# StartStopSwitch.net
KiCad netlist of a schematic drawn in EAGLE
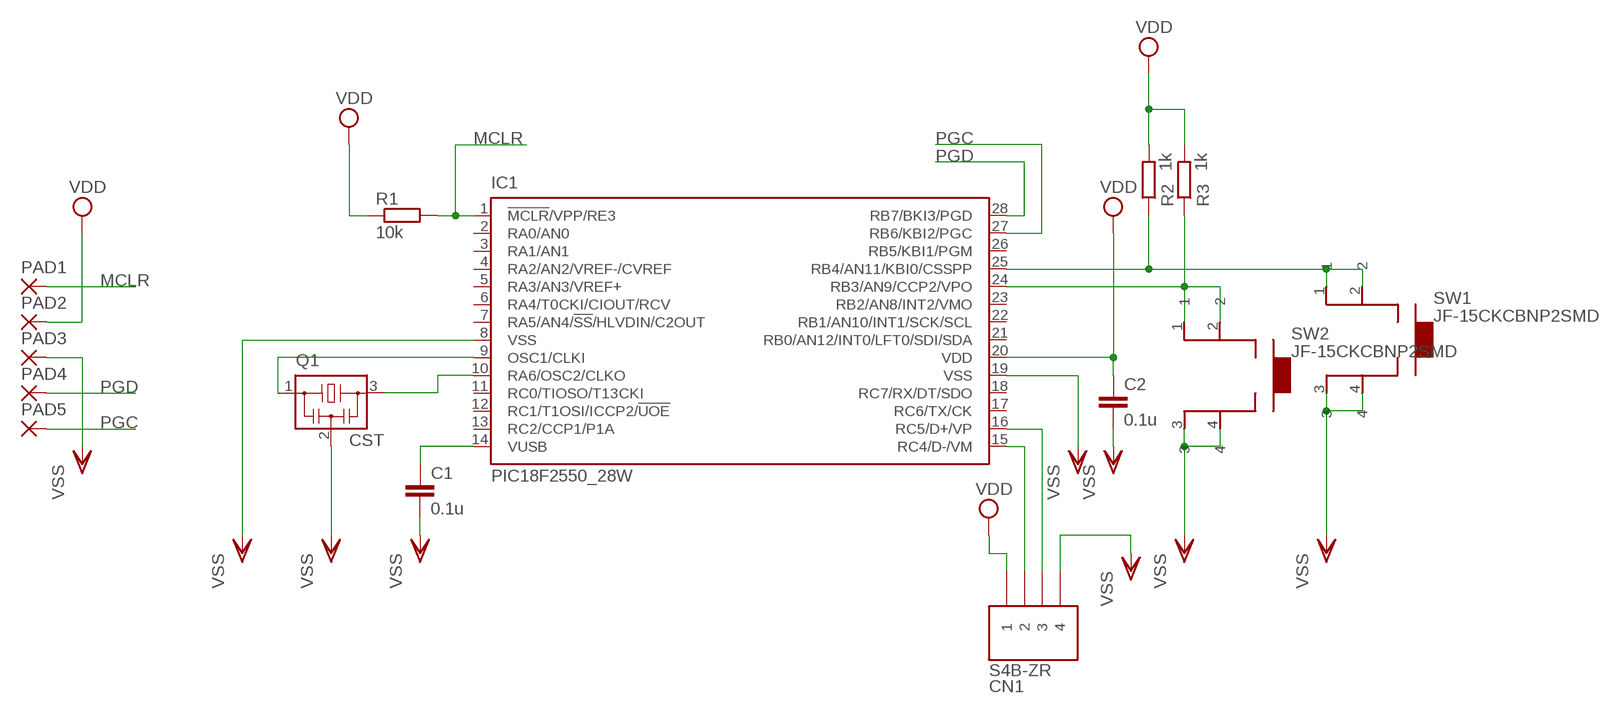
[diagram p0: schematic, sheet 1]

(export (version "E")
  (design (tool "Eeschema 10.0.6"))
  (components
    (comp (ref "C1")
      (value "0.1u")
      (footprint "eagle-import:C2012")
      (libsource (lib "eagle-import") (part "C-EUC2012"))
    )
    (comp (ref "C2")
      (value "0.1u")
      (footprint "eagle-import:C2012")
      (libsource (lib "eagle-import") (part "C-EUC2012"))
    )
    (comp (ref "CN1")
      (value "S4B-ZR")
      (footprint "eagle-import:S4B-ZR")
      (libsource (lib "eagle-import") (part "S4B-ZR"))
    )
    (comp (ref "IC1")
      (value "PIC18F2550_28W")
      (footprint "eagle-import:SO28W")
      (fields (field (name "MF") "MICROCHIP") (field (name "MPN") "PIC18F2550-I/SO"))
      (libsource (lib "eagle-import") (part "PIC18F2_28W550"))
    )
    (comp (ref "PAD1")
      (value "WIREPADSMD1,27-254")
      (footprint "eagle-import:SMD1,27-2,54")
      (libsource (lib "eagle-import") (part "WIREPADSMD1,27-254"))
    )
    (comp (ref "PAD2")
      (value "WIREPADSMD1,27-254")
      (footprint "eagle-import:SMD1,27-2,54")
      (libsource (lib "eagle-import") (part "WIREPADSMD1,27-254"))
    )
    (comp (ref "PAD3")
      (value "WIREPADSMD1,27-254")
      (footprint "eagle-import:SMD1,27-2,54")
      (libsource (lib "eagle-import") (part "WIREPADSMD1,27-254"))
    )
    (comp (ref "PAD4")
      (value "WIREPADSMD1,27-254")
      (footprint "eagle-import:SMD1,27-2,54")
      (libsource (lib "eagle-import") (part "WIREPADSMD1,27-254"))
    )
    (comp (ref "PAD5")
      (value "WIREPADSMD1,27-254")
      (footprint "eagle-import:SMD1,27-2,54")
      (libsource (lib "eagle-import") (part "WIREPADSMD1,27-254"))
    )
    (comp (ref "Q1")
      (value "CST")
      (footprint "eagle-import:CSTCR6M-MINI")
      (libsource (lib "eagle-import") (part "CSTCRMINI"))
    )
    (comp (ref "R1")
      (value "10k")
      (footprint "eagle-import:R0805")
      (libsource (lib "eagle-import") (part "R-EU_R0805"))
    )
    (comp (ref "R2")
      (value "1k")
      (footprint "eagle-import:R0805")
      (libsource (lib "eagle-import") (part "R-EU_R0805"))
    )
    (comp (ref "R3")
      (value "1k")
      (footprint "eagle-import:R0805")
      (libsource (lib "eagle-import") (part "R-EU_R0805"))
    )
    (comp (ref "SW1")
      (value "JF-15CKCBNP2SMD")
      (footprint "eagle-import:JF-15CKCBNP2-SMD")
      (libsource (lib "eagle-import") (part "JF-15CKCBNP2SMD"))
    )
    (comp (ref "SW2")
      (value "JF-15CKCBNP2SMD")
      (footprint "eagle-import:JF-15CKCBNP2-SMD")
      (libsource (lib "eagle-import") (part "JF-15CKCBNP2SMD"))
    )
  )
  (nets
    (net (code "1") (name "/MCLR") (class "Default")
      (node (ref "IC1") (pin "1") (pinfunction "~{MCLR}/VPP/RE3_1") (pintype "input"))
      (node (ref "PAD1") (pin "1") (pinfunction "P_1") (pintype "passive"))
      (node (ref "R1") (pin "2") (pinfunction "2_2") (pintype "passive"))
    )
    (net (code "2") (name "/PGC") (class "Default")
      (node (ref "IC1") (pin "27") (pinfunction "RB6/KBI2/PGC_27") (pintype "bidirectional"))
      (node (ref "PAD5") (pin "1") (pinfunction "P_1") (pintype "passive"))
    )
    (net (code "3") (name "/PGD") (class "Default")
      (node (ref "IC1") (pin "28") (pinfunction "RB7/BKI3/PGD_28") (pintype "bidirectional"))
      (node (ref "PAD4") (pin "1") (pinfunction "P_1") (pintype "passive"))
    )
    (net (code "4") (name "Net-(IC1-OSC1{slash}CLKI)") (class "Default")
      (node (ref "IC1") (pin "9") (pinfunction "OSC1/CLKI_9") (pintype "input"))
      (node (ref "Q1") (pin "1") (pinfunction "1_1") (pintype "passive"))
    )
    (net (code "5") (name "Net-(IC1-RA6{slash}OSC2{slash}CLKO)") (class "Default")
      (node (ref "IC1") (pin "10") (pinfunction "RA6/OSC2/CLKO_10") (pintype "output"))
      (node (ref "Q1") (pin "3") (pinfunction "3_3") (pintype "passive"))
    )
    (net (code "6") (name "Net-(IC1-RB3{slash}AN9{slash}CCP2{slash}VPO)") (class "Default")
      (node (ref "IC1") (pin "24") (pinfunction "RB3/AN9/CCP2/VPO_24") (pintype "bidirectional"))
      (node (ref "R3") (pin "1") (pinfunction "1_1") (pintype "passive"))
      (node (ref "SW2") (pin "1") (pinfunction "1_1") (pintype "bidirectional"))
      (node (ref "SW2") (pin "2") (pinfunction "2_2") (pintype "bidirectional"))
    )
    (net (code "7") (name "Net-(IC1-RB4{slash}AN11{slash}KBI0{slash}CSSPP)") (class "Default")
      (node (ref "IC1") (pin "25") (pinfunction "RB4/AN11/KBI0/CSSPP_25") (pintype "bidirectional"))
      (node (ref "R2") (pin "1") (pinfunction "1_1") (pintype "passive"))
      (node (ref "SW1") (pin "1") (pinfunction "1_1") (pintype "bidirectional"))
      (node (ref "SW1") (pin "2") (pinfunction "2_2") (pintype "bidirectional"))
    )
    (net (code "8") (name "Net-(IC1-RC4{slash}D-{slash}VM)") (class "Default")
      (node (ref "CN1") (pin "2") (pinfunction "2_2") (pintype "bidirectional"))
      (node (ref "IC1") (pin "15") (pinfunction "RC4/D-/VM_15") (pintype "bidirectional"))
    )
    (net (code "9") (name "Net-(IC1-RC5{slash}D+{slash}VP)") (class "Default")
      (node (ref "CN1") (pin "3") (pinfunction "3_3") (pintype "bidirectional"))
      (node (ref "IC1") (pin "16") (pinfunction "RC5/D+/VP_16") (pintype "bidirectional"))
    )
    (net (code "10") (name "Net-(IC1-VUSB)") (class "Default")
      (node (ref "C1") (pin "1") (pinfunction "1_1") (pintype "passive"))
      (node (ref "IC1") (pin "14") (pinfunction "VUSB_14") (pintype "bidirectional"))
    )
    (net (code "11") (name "VDD") (class "Default")
      (node (ref "C2") (pin "1") (pinfunction "1_1") (pintype "passive"))
      (node (ref "CN1") (pin "1") (pinfunction "1_1") (pintype "bidirectional"))
      (node (ref "IC1") (pin "20") (pinfunction "VDD_20") (pintype "power_in"))
      (node (ref "PAD2") (pin "1") (pinfunction "P_1") (pintype "passive"))
      (node (ref "R1") (pin "1") (pinfunction "1_1") (pintype "passive"))
      (node (ref "R2") (pin "2") (pinfunction "2_2") (pintype "passive"))
      (node (ref "R3") (pin "2") (pinfunction "2_2") (pintype "passive"))
    )
    (net (code "12") (name "VSS") (class "Default")
      (node (ref "C1") (pin "2") (pinfunction "2_2") (pintype "passive"))
      (node (ref "C2") (pin "2") (pinfunction "2_2") (pintype "passive"))
      (node (ref "CN1") (pin "4") (pinfunction "4_4") (pintype "bidirectional"))
      (node (ref "IC1") (pin "19") (pinfunction "VSS_19") (pintype "power_in"))
      (node (ref "IC1") (pin "8") (pinfunction "VSS_8") (pintype "power_in"))
      (node (ref "PAD3") (pin "1") (pinfunction "P_1") (pintype "passive"))
      (node (ref "Q1") (pin "2") (pinfunction "2_2") (pintype "passive"))
      (node (ref "SW1") (pin "3") (pinfunction "3_3") (pintype "bidirectional"))
      (node (ref "SW1") (pin "4") (pinfunction "4_4") (pintype "bidirectional"))
      (node (ref "SW2") (pin "3") (pinfunction "3_3") (pintype "bidirectional"))
      (node (ref "SW2") (pin "4") (pinfunction "4_4") (pintype "bidirectional"))
    )
    (net (code "13") (name "unconnected-(IC1-RA0{slash}AN0-Pad2)") (class "Default")
      (node (ref "IC1") (pin "2") (pinfunction "RA0/AN0_2") (pintype "bidirectional"))
    )
    (net (code "14") (name "unconnected-(IC1-RA1{slash}AN1-Pad3)") (class "Default")
      (node (ref "IC1") (pin "3") (pinfunction "RA1/AN1_3") (pintype "bidirectional"))
    )
    (net (code "15") (name "unconnected-(IC1-RA2{slash}AN2{slash}VREF-{slash}CVREF-Pad4)") (class "Default")
      (node (ref "IC1") (pin "4") (pinfunction "RA2/AN2/VREF-/CVREF_4") (pintype "bidirectional"))
    )
    (net (code "16") (name "unconnected-(IC1-RA3{slash}AN3{slash}VREF+-Pad5)") (class "Default")
      (node (ref "IC1") (pin "5") (pinfunction "RA3/AN3/VREF+_5") (pintype "bidirectional"))
    )
    (net (code "17") (name "unconnected-(IC1-RA4{slash}T0CKI{slash}CIOUT{slash}RCV-Pad6)") (class "Default")
      (node (ref "IC1") (pin "6") (pinfunction "RA4/T0CKI/CIOUT/RCV_6") (pintype "bidirectional"))
    )
    (net (code "18") (name "unconnected-(IC1-RA5{slash}AN4{slash}~{SS}{slash}HLVDIN{slash}C2OUT-Pad7)") (class "Default")
      (node (ref "IC1") (pin "7") (pinfunction "RA5/AN4/~{SS}/HLVDIN/C2OUT_7") (pintype "bidirectional"))
    )
    (net (code "19") (name "unconnected-(IC1-RB0{slash}AN12{slash}INT0{slash}LFT0{slash}SDI{slash}SDA-Pad21)") (class "Default")
      (node (ref "IC1") (pin "21") (pinfunction "RB0/AN12/INT0/LFT0/SDI/SDA_21") (pintype "bidirectional"))
    )
    (net (code "20") (name "unconnected-(IC1-RB1{slash}AN10{slash}INT1{slash}SCK{slash}SCL-Pad22)") (class "Default")
      (node (ref "IC1") (pin "22") (pinfunction "RB1/AN10/INT1/SCK/SCL_22") (pintype "bidirectional"))
    )
    (net (code "21") (name "unconnected-(IC1-RB2{slash}AN8{slash}INT2{slash}VMO-Pad23)") (class "Default")
      (node (ref "IC1") (pin "23") (pinfunction "RB2/AN8/INT2/VMO_23") (pintype "bidirectional"))
    )
    (net (code "22") (name "unconnected-(IC1-RB5{slash}KBI1{slash}PGM-Pad26)") (class "Default")
      (node (ref "IC1") (pin "26") (pinfunction "RB5/KBI1/PGM_26") (pintype "bidirectional"))
    )
    (net (code "23") (name "unconnected-(IC1-RC0{slash}TIOSO{slash}T13CKI-Pad11)") (class "Default")
      (node (ref "IC1") (pin "11") (pinfunction "RC0/TIOSO/T13CKI_11") (pintype "bidirectional"))
    )
    (net (code "24") (name "unconnected-(IC1-RC1{slash}T1OSI{slash}ICCP2{slash}~{UOE}-Pad12)") (class "Default")
      (node (ref "IC1") (pin "12") (pinfunction "RC1/T1OSI/ICCP2/~{UOE}_12") (pintype "bidirectional"))
    )
    (net (code "25") (name "unconnected-(IC1-RC2{slash}CCP1{slash}P1A-Pad13)") (class "Default")
      (node (ref "IC1") (pin "13") (pinfunction "RC2/CCP1/P1A_13") (pintype "bidirectional"))
    )
    (net (code "26") (name "unconnected-(IC1-RC6{slash}TX{slash}CK-Pad17)") (class "Default")
      (node (ref "IC1") (pin "17") (pinfunction "RC6/TX/CK_17") (pintype "bidirectional"))
    )
    (net (code "27") (name "unconnected-(IC1-RC7{slash}RX{slash}DT{slash}SDO-Pad18)") (class "Default")
      (node (ref "IC1") (pin "18") (pinfunction "RC7/RX/DT/SDO_18") (pintype "bidirectional"))
    )
  )
)
